# 05A-010.net
KiCad netlist of a schematic drawn in EAGLE
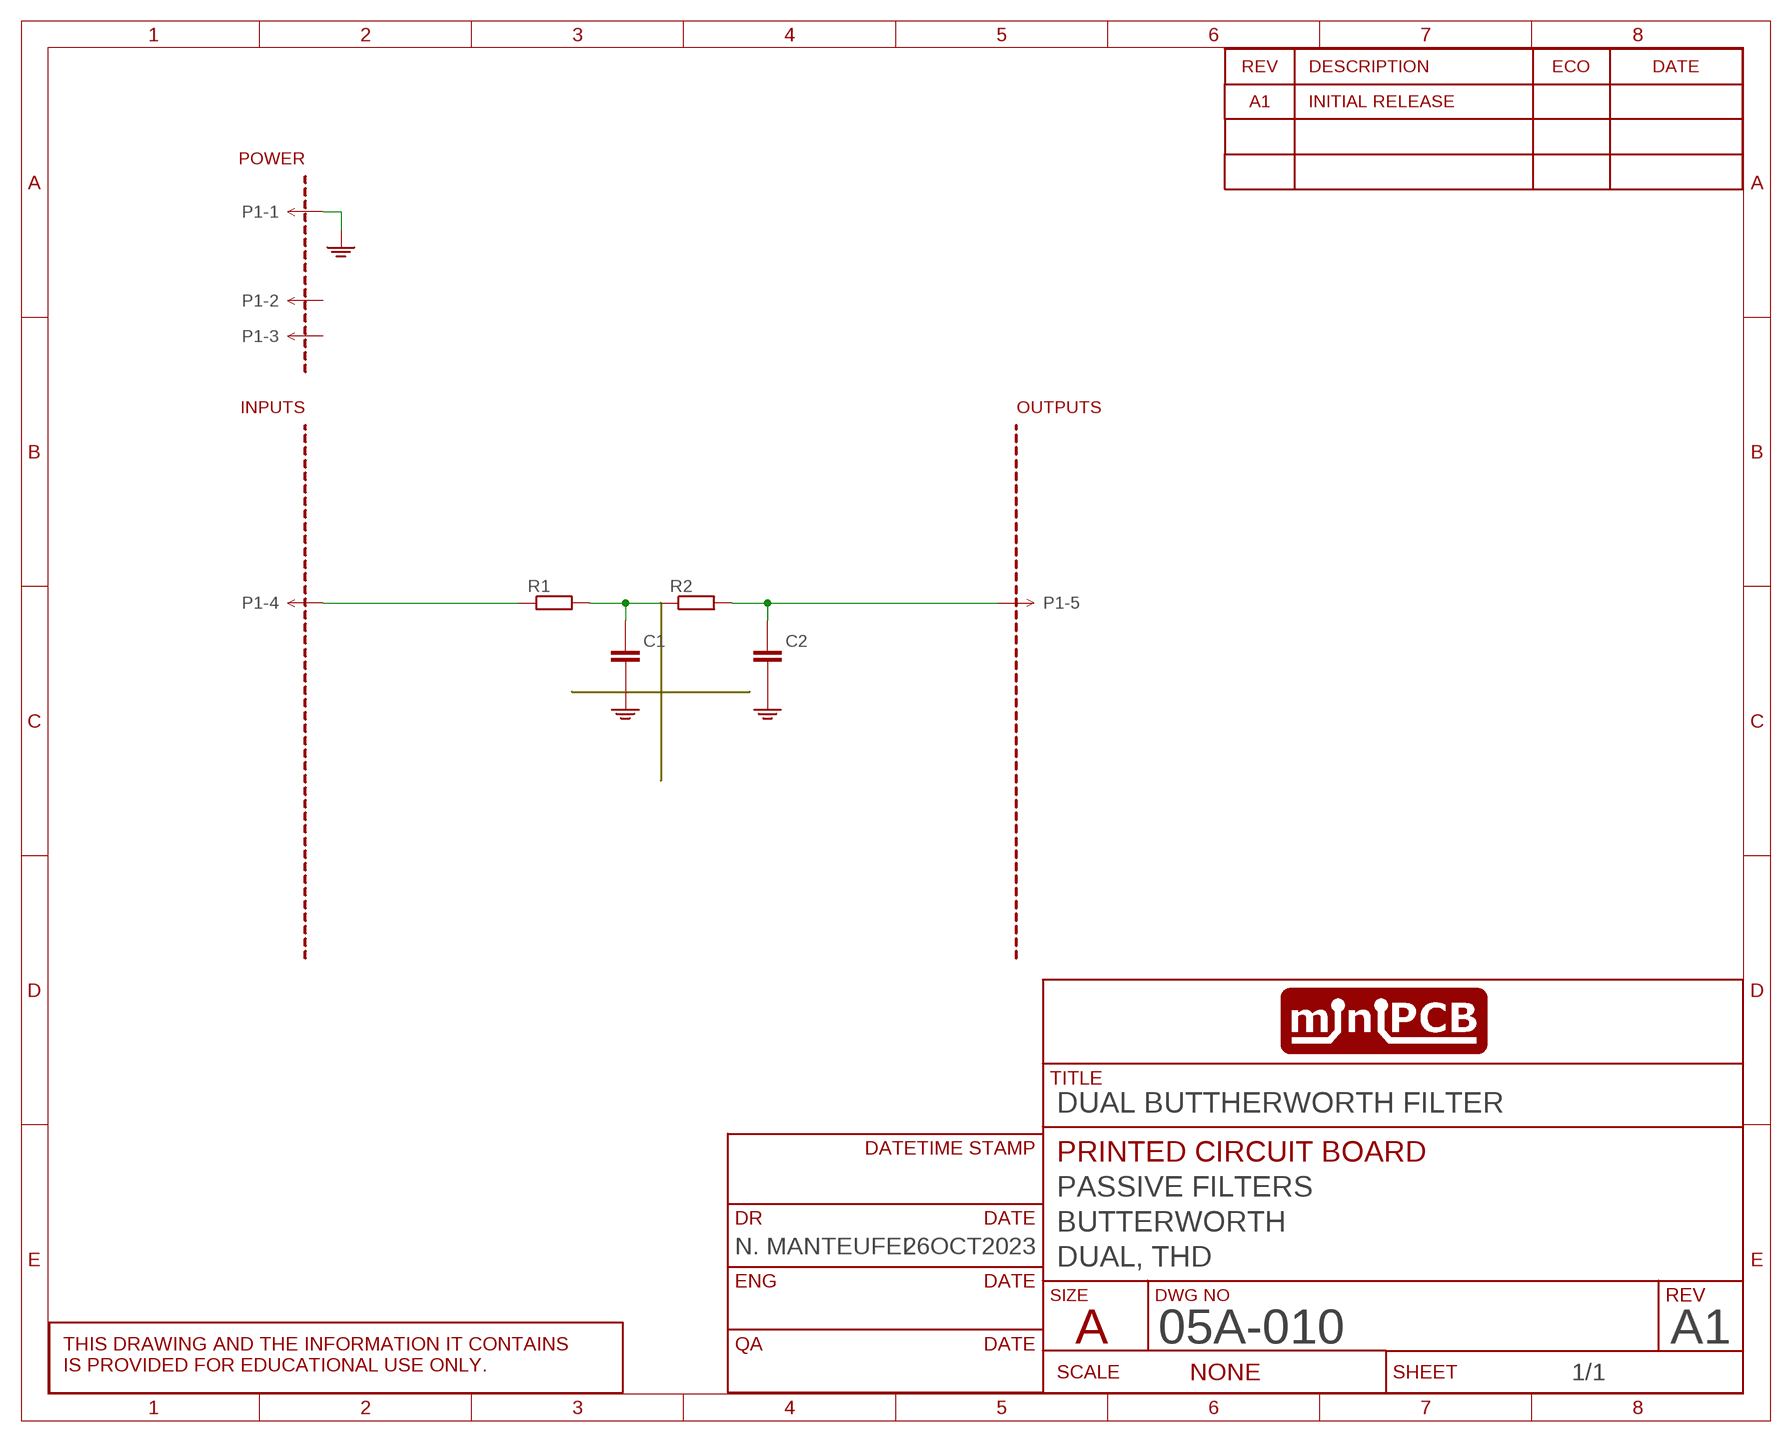
[diagram p0: schematic, sheet 1]

(export (version "E")
  (design (tool "Eeschema 10.0.6"))
  (components
    (comp (ref "C1")
      (value "CAPACITORTHD")
      (footprint "eagle-import:C050-024X044")
      (libsource (lib "eagle-import") (part "CAPACITORTHD"))
    )
    (comp (ref "C2")
      (value "CAPACITORTHD")
      (footprint "eagle-import:C050-024X044")
      (libsource (lib "eagle-import") (part "CAPACITORTHD"))
    )
    (comp (ref "P1")
      (value "MINIPCB_5P5P")
      (footprint "eagle-import:PINS_1X5")
      (libsource (lib "eagle-import") (part "MINIPCB_5P5P"))
    )
    (comp (ref "PCB1")
      (value "MINIPCB_0P00A-20X33")
      (footprint "eagle-import:MINIPCB_00A_20X33")
      (libsource (lib "eagle-import") (part "MINIPCB_0P00A-20X33"))
    )
    (comp (ref "R1")
      (value "RESISTORTHD")
      (footprint "eagle-import:0204_10")
      (libsource (lib "eagle-import") (part "RESISTORTHD"))
    )
    (comp (ref "R2")
      (value "RESISTORTHD")
      (footprint "eagle-import:0204_10")
      (libsource (lib "eagle-import") (part "RESISTORTHD"))
    )
  )
  (nets
    (net (code "1") (name "GND") (class "Default")
      (node (ref "C1") (pin "2") (pinfunction "-_2") (pintype "passive"))
      (node (ref "C2") (pin "2") (pinfunction "-_2") (pintype "passive"))
      (node (ref "P1") (pin "1") (pinfunction "1_1") (pintype "bidirectional"))
    )
    (net (code "2") (name "Net-(C1-+)") (class "Default")
      (node (ref "C1") (pin "1") (pinfunction "+_1") (pintype "passive"))
      (node (ref "R1") (pin "2") (pinfunction "2_2") (pintype "passive"))
      (node (ref "R2") (pin "1") (pinfunction "1_1") (pintype "passive"))
    )
    (net (code "3") (name "Net-(C2-+)") (class "Default")
      (node (ref "C2") (pin "1") (pinfunction "+_1") (pintype "passive"))
      (node (ref "P1") (pin "5") (pinfunction "1_5") (pintype "bidirectional"))
      (node (ref "R2") (pin "2") (pinfunction "2_2") (pintype "passive"))
    )
    (net (code "4") (name "Net-(P1D-1)") (class "Default")
      (node (ref "P1") (pin "4") (pinfunction "1_4") (pintype "bidirectional"))
      (node (ref "R1") (pin "1") (pinfunction "1_1") (pintype "passive"))
    )
    (net (code "5") (name "unconnected-(P1B-1-Pad2)") (class "Default")
      (node (ref "P1") (pin "2") (pinfunction "1_2") (pintype "bidirectional"))
    )
    (net (code "6") (name "unconnected-(P1C-1-Pad3)") (class "Default")
      (node (ref "P1") (pin "3") (pinfunction "1_3") (pintype "bidirectional"))
    )
  )
)
